# USB.net
KiCad netlist of a schematic drawn in Altium Designer
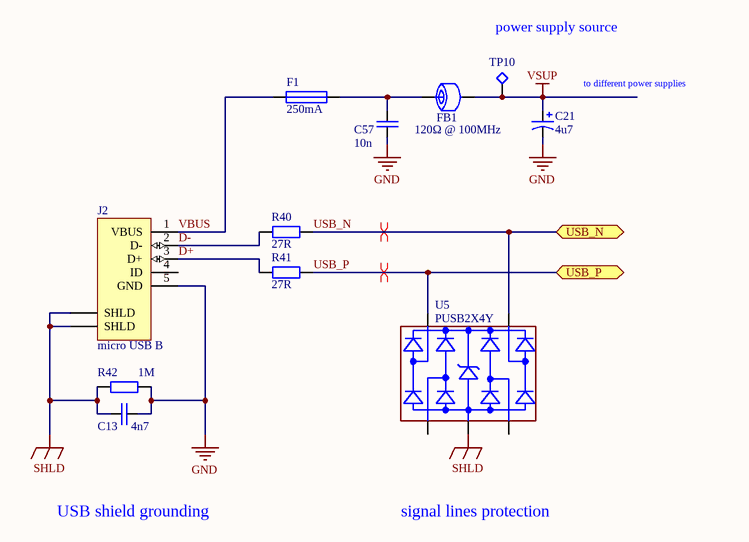
[diagram p0: USB.SchDoc]

(export (version "E")
  (design (tool "Eeschema 10.0.6"))
  (components
    (comp (ref "C13")
      (value "4n7")
      (footprint "C_0603")
      (description "Generic capacitor")
      (libsource (lib "DAQ_REV_B") (part "Capacitor"))
    )
    (comp (ref "C21")
      (value "4u7")
      (footprint "Tantalum Case A")
      (description "Generic polarized capacitor")
      (libsource (lib "DAQ_REV_B") (part "Capacitor - polarized"))
    )
    (comp (ref "C57")
      (value "10n")
      (footprint "C_0603")
      (description "Generic capacitor")
      (libsource (lib "DAQ_REV_B") (part "Capacitor"))
    )
    (comp (ref "F1")
      (value "250mA")
      (footprint "PPTCF 1206")
      (description "Resettable Fuse, PPTC, 1206 (3216 Metric), POLYFUSE 1206L Series, 16 VDC, 250 mA, 500 mA, 0.08 s")
      (fields (field (name "MANUFACTURER") "Littelfuse"))
      (libsource (lib "DAQ_REV_B") (part "1206L025YR"))
    )
    (comp (ref "FB1")
      (value "120Ω @ 100MHz")
      (footprint "SMD_0805")
      (description "Ferrite Bead, 0805 [2012 Metric], 120 ohm, 800 mA, BLM21A Series, 0.15 ohm, ± 25%")
      (fields (field (name "MANUFACTURER") "Murata"))
      (libsource (lib "DAQ_REV_B") (part "BLM21AG121SN1D"))
    )
    (comp (ref "J2")
      (value "micro USB B")
      (footprint "MICRO_USB_A")
      (description "USB Connector, Micro USB Type AB, USB 2.0, Receptacle, 5 Ways, Surface Mount, Right Angle")
      (fields (field (name "MANUFACTURER") "FCI"))
      (libsource (lib "DAQ_REV_B") (part "10104111-0001LF"))
    )
    (comp (ref "R40")
      (value "27R")
      (footprint "R_0603")
      (description "Generic resistor")
      (libsource (lib "DAQ_REV_B") (part "Resistor"))
    )
    (comp (ref "R41")
      (value "27R")
      (footprint "R_0603")
      (description "Generic resistor")
      (libsource (lib "DAQ_REV_B") (part "Resistor"))
    )
    (comp (ref "R42")
      (value "1M")
      (footprint "R_0603")
      (description "Generic resistor")
      (libsource (lib "DAQ_REV_B") (part "Resistor"))
    )
    (comp (ref "TP10")
      (value "testpoint")
      (footprint "TP1_FULL")
      (description "testpoint 1.5mm diameter no hole")
      (fields (field (name "PART NUMBER") "XXC0006"))
      (libsource (lib "DAQ_REV_B") (part "Test Point"))
    )
    (comp (ref "U5")
      (value "PUSB2X4Y")
      (footprint "SOT363")
      (description "ESD protection for high-speed interfaces")
      (fields (field (name "PART NUMBER") "XDE0000") (field (name "MANUFACTURER") "Multicomp"))
      (libsource (lib "DAQ_REV_B") (part "PUSB2X4Y"))
    )
  )
  (nets
    (net (code "1") (name "/D+") (class "Default")
      (node (ref "J2") (pin "3") (pinfunction "D+_3") (pintype "bidirectional"))
      (node (ref "R41") (pin "1") (pintype "passive"))
    )
    (net (code "2") (name "/D-") (class "Default")
      (node (ref "J2") (pin "2") (pinfunction "D-_2") (pintype "bidirectional"))
      (node (ref "R40") (pin "1") (pintype "passive"))
    )
    (net (code "3") (name "/USB_N") (class "Default")
      (node (ref "R40") (pin "2") (pintype "passive"))
      (node (ref "U5") (pin "4") (pinfunction "4_4") (pintype "passive"))
    )
    (net (code "4") (name "/USB_P") (class "Default")
      (node (ref "R41") (pin "2") (pintype "passive"))
      (node (ref "U5") (pin "6") (pinfunction "6_6") (pintype "passive"))
    )
    (net (code "5") (name "/VBUS") (class "Default")
      (node (ref "F1") (pin "1") (pinfunction "1_1") (pintype "passive"))
      (node (ref "J2") (pin "1") (pinfunction "VBUS_1") (pintype "power_in"))
    )
    (net (code "6") (name "GND") (class "Default")
      (node (ref "C13") (pin "1") (pinfunction "1_1") (pintype "passive"))
      (node (ref "C21") (pin "2") (pinfunction "2_2") (pintype "passive"))
      (node (ref "C57") (pin "2") (pinfunction "2_2") (pintype "passive"))
      (node (ref "J2") (pin "5") (pinfunction "GND_5") (pintype "power_in"))
      (node (ref "R42") (pin "1") (pintype "passive"))
    )
    (net (code "7") (name "Net-(C57-Pad1)") (class "Default")
      (node (ref "C57") (pin "1") (pinfunction "1_1") (pintype "passive"))
      (node (ref "F1") (pin "2") (pinfunction "2_2") (pintype "passive"))
      (node (ref "FB1") (pin "1") (pintype "passive"))
    )
    (net (code "8") (name "SHLD") (class "Default")
      (node (ref "C13") (pin "2") (pinfunction "2_2") (pintype "passive"))
      (node (ref "J2") (pin "6") (pinfunction "SHLD_6") (pintype "passive"))
      (node (ref "J2") (pin "7") (pinfunction "SHLD_7") (pintype "passive"))
      (node (ref "R42") (pin "2") (pintype "passive"))
      (node (ref "U5") (pin "2") (pinfunction "2_2") (pintype "passive"))
    )
    (net (code "9") (name "VSUP") (class "Default")
      (node (ref "C21") (pin "1") (pinfunction "1_1") (pintype "passive"))
      (node (ref "FB1") (pin "2") (pintype "passive"))
      (node (ref "TP10") (pin "1") (pinfunction "1_1") (pintype "passive"))
    )
    (net (code "10") (name "unconnected-(J2-ID-Pad4)") (class "Default")
      (node (ref "J2") (pin "4") (pinfunction "ID_4") (pintype "passive"))
    )
    (net (code "11") (name "unconnected-(U5-Pad1)") (class "Default")
      (node (ref "U5") (pin "1") (pinfunction "1_1") (pintype "passive"))
    )
    (net (code "12") (name "unconnected-(U5-Pad3)") (class "Default")
      (node (ref "U5") (pin "3") (pinfunction "3_3") (pintype "passive"))
    )
  )
)
